# Power.net
KiCad netlist of a schematic drawn in Altium Designer
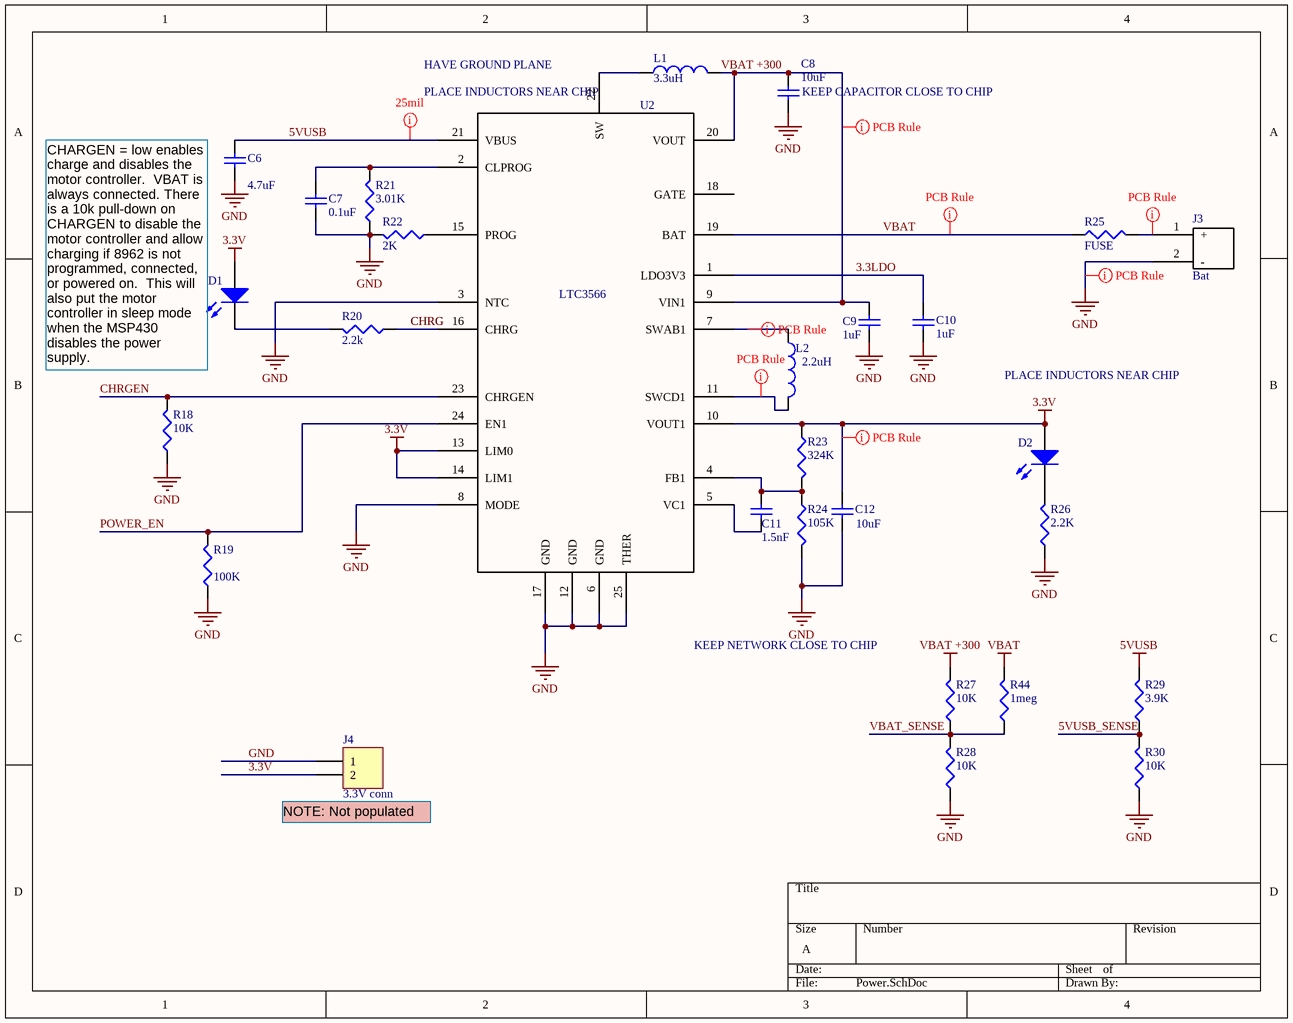
[diagram p0: Power.SchDoc]

(export (version "E")
  (design (tool "Eeschema 10.0.6"))
  (components
    (comp (ref "C6")
      (value "4.7uF")
      (footprint "CAPC1005L")
      (description "Capacitor (Semiconductor SIM Model)")
      (fields (field (name "Comment") "Cap Semi") (field (name "PUBLISHER") "Altium Limited"))
      (libsource (lib "Miscellaneous Devices") (part "Cap Semi"))
    )
    (comp (ref "C7")
      (value "0.1uF")
      (footprint "CAPC1005L")
      (description "Capacitor")
      (fields (field (name "Comment") "Cap") (field (name "PUBLISHER") "Altium Limited"))
      (libsource (lib "Miscellaneous Devices") (part "Cap"))
    )
    (comp (ref "C8")
      (value "10uF")
      (footprint "CAPC1608L")
      (description "Capacitor")
      (fields (field (name "Comment") "Cap") (field (name "PUBLISHER") "Altium Limited"))
      (libsource (lib "Miscellaneous Devices") (part "Cap"))
    )
    (comp (ref "C9")
      (value "1uF")
      (footprint "CAPC1608L")
      (description "Capacitor")
      (fields (field (name "Comment") "Cap") (field (name "PUBLISHER") "Altium Limited"))
      (libsource (lib "Miscellaneous Devices") (part "Cap"))
    )
    (comp (ref "C10")
      (value "1uF")
      (footprint "CAPC1608L")
      (description "Capacitor")
      (fields (field (name "Comment") "Cap") (field (name "PUBLISHER") "Altium Limited"))
      (libsource (lib "Miscellaneous Devices") (part "Cap"))
    )
    (comp (ref "C11")
      (value "1.5nF")
      (footprint "CAPC1005L")
      (description "Capacitor")
      (fields (field (name "Comment") "Cap") (field (name "PUBLISHER") "Altium Limited"))
      (libsource (lib "Miscellaneous Devices") (part "Cap"))
    )
    (comp (ref "C12")
      (value "10uF")
      (footprint "CAPC1608L")
      (description "Capacitor")
      (fields (field (name "Comment") "Cap") (field (name "PUBLISHER") "Altium Limited"))
      (libsource (lib "Miscellaneous Devices") (part "Cap"))
    )
    (comp (ref "D1")
      (value "Charge")
      (footprint "INDC2012L")
      (description "Typical RED, GREEN, YELLOW, AMBER GaAs LED")
      (fields (field (name "PUBLISHER") "Altium Limited"))
      (libsource (lib "Miscellaneous Devices") (part "LED2"))
    )
    (comp (ref "D2")
      (value "Power")
      (footprint "INDC2012L")
      (description "Typical RED, GREEN, YELLOW, AMBER GaAs LED")
      (fields (field (name "PUBLISHER") "Altium Limited"))
      (libsource (lib "Miscellaneous Devices") (part "LED2"))
    )
    (comp (ref "J3")
      (value "Bat")
      (footprint "BatteryConnJST")
      (libsource (lib "mrone") (part "BatteryConnJST"))
    )
    (comp (ref "J4")
      (value "3.3V conn")
      (footprint "HDR1X2")
      (description "Header, 2-Pin")
      (fields (field (name "PUBLISHER") "Altium Limited"))
      (libsource (lib "Miscellaneous Connectors") (part "Header 2"))
    )
    (comp (ref "L1") (value "3.3uH") (footprint "IndPow") (libsource (lib "mrone") (part "Inductor")))
    (comp (ref "L2") (value "2.2uH") (footprint "IndPow") (libsource (lib "mrone") (part "Inductor")))
    (comp (ref "R18")
      (value "10K")
      (footprint "RESC1608L")
      (description "Resistor")
      (fields (field (name "Comment") "Res3") (field (name "PUBLISHER") "Altium Limited"))
      (libsource (lib "Miscellaneous Devices") (part "Res3"))
    )
    (comp (ref "R19")
      (value "100K")
      (footprint "RESC1608L")
      (description "Resistor")
      (fields (field (name "Comment") "Res3") (field (name "PUBLISHER") "Altium Limited"))
      (libsource (lib "Miscellaneous Devices") (part "Res3"))
    )
    (comp (ref "R20")
      (value "2.2k")
      (footprint "RESC1608L")
      (description "Resistor")
      (fields (field (name "Comment") "Res3") (field (name "PUBLISHER") "Altium Limited"))
      (libsource (lib "Miscellaneous Devices") (part "Res3"))
    )
    (comp (ref "R21")
      (value "3.01K")
      (footprint "RESC1608L")
      (description "Resistor")
      (fields (field (name "Comment") "Res3") (field (name "PUBLISHER") "Altium Limited"))
      (libsource (lib "Miscellaneous Devices") (part "Res3"))
    )
    (comp (ref "R22")
      (value "2K")
      (footprint "RESC1608L")
      (description "Resistor")
      (fields (field (name "Comment") "Res3") (field (name "PUBLISHER") "Altium Limited"))
      (libsource (lib "Miscellaneous Devices") (part "Res3"))
    )
    (comp (ref "R23")
      (value "324K")
      (footprint "RESC1608L")
      (description "Resistor")
      (fields (field (name "Comment") "Res3") (field (name "PUBLISHER") "Altium Limited"))
      (libsource (lib "Miscellaneous Devices") (part "Res3"))
    )
    (comp (ref "R24")
      (value "105K")
      (footprint "RESC1608L")
      (description "Resistor")
      (fields (field (name "Comment") "Res3") (field (name "PUBLISHER") "Altium Limited"))
      (libsource (lib "Miscellaneous Devices") (part "Res3"))
    )
    (comp (ref "R25")
      (value "FUSE")
      (footprint "RESC3225L")
      (description "Resistor")
      (fields (field (name "Comment") "Res3") (field (name "PUBLISHER") "Altium Limited"))
      (libsource (lib "Miscellaneous Devices") (part "Res3"))
    )
    (comp (ref "R26")
      (value "2.2K")
      (footprint "RESC1608L")
      (description "Resistor")
      (fields (field (name "Comment") "Res3") (field (name "PUBLISHER") "Altium Limited"))
      (libsource (lib "Miscellaneous Devices") (part "Res3"))
    )
    (comp (ref "R27")
      (value "10K")
      (footprint "RESC1608L")
      (description "Resistor")
      (fields (field (name "Comment") "Res3") (field (name "PUBLISHER") "Altium Limited"))
      (libsource (lib "Miscellaneous Devices") (part "Res3"))
    )
    (comp (ref "R28")
      (value "10K")
      (footprint "RESC1608L")
      (description "Resistor")
      (fields (field (name "Comment") "Res3") (field (name "PUBLISHER") "Altium Limited"))
      (libsource (lib "Miscellaneous Devices") (part "Res3"))
    )
    (comp (ref "R29")
      (value "3.9K")
      (footprint "RESC1608L")
      (description "Resistor")
      (fields (field (name "Comment") "Res3") (field (name "PUBLISHER") "Altium Limited"))
      (libsource (lib "Miscellaneous Devices") (part "Res3"))
    )
    (comp (ref "R30")
      (value "10K")
      (footprint "RESC1608L")
      (description "Resistor")
      (fields (field (name "Comment") "Res3") (field (name "PUBLISHER") "Altium Limited"))
      (libsource (lib "Miscellaneous Devices") (part "Res3"))
    )
    (comp (ref "R44")
      (value "1meg")
      (footprint "RESC1608L")
      (description "Resistor")
      (fields (field (name "Comment") "Res3") (field (name "PUBLISHER") "Altium Limited"))
      (libsource (lib "Miscellaneous Devices") (part "Res3"))
    )
    (comp (ref "U2")
      (value "LTC3566")
      (footprint "QFN-24")
      (libsource (lib "Schematic Components") (part "LTC3566"))
    )
  )
  (nets
    (net (code "1") (name "/3.3LDO") (class "Default")
      (node (ref "C10") (pin "1") (pinfunction "1_1") (pintype "passive"))
      (node (ref "U2") (pin "1") (pinfunction "LDO3V3_1") (pintype "passive"))
    )
    (net (code "2") (name "/5VUSB_SENSE") (class "Default")
      (node (ref "R29") (pin "1") (pinfunction "1_1") (pintype "passive"))
      (node (ref "R30") (pin "2") (pinfunction "2_2") (pintype "passive"))
    )
    (net (code "3") (name "/CHRG") (class "Default")
      (node (ref "R20") (pin "1") (pinfunction "1_1") (pintype "passive"))
      (node (ref "U2") (pin "16") (pinfunction "CHRG_16") (pintype "passive"))
    )
    (net (code "4") (name "/CHRGEN") (class "Default")
      (node (ref "R18") (pin "2") (pinfunction "2_2") (pintype "passive"))
      (node (ref "U2") (pin "23") (pinfunction "CHRGEN_23") (pintype "passive"))
    )
    (net (code "5") (name "/POWER_EN") (class "Default")
      (node (ref "R19") (pin "2") (pinfunction "2_2") (pintype "passive"))
      (node (ref "U2") (pin "24") (pinfunction "EN1_24") (pintype "passive"))
    )
    (net (code "6") (name "/VBAT_SENSE") (class "Default")
      (node (ref "R27") (pin "1") (pinfunction "1_1") (pintype "passive"))
      (node (ref "R28") (pin "2") (pinfunction "2_2") (pintype "passive"))
      (node (ref "R44") (pin "1") (pinfunction "1_1") (pintype "passive"))
    )
    (net (code "7") (name "3.3V") (class "Default")
      (node (ref "C12") (pin "2") (pinfunction "2_2") (pintype "passive"))
      (node (ref "D1") (pin "1") (pinfunction "A_1") (pintype "passive"))
      (node (ref "D2") (pin "1") (pinfunction "A_1") (pintype "passive"))
      (node (ref "J4") (pin "2") (pinfunction "2_2") (pintype "passive"))
      (node (ref "R23") (pin "1") (pinfunction "1_1") (pintype "passive"))
      (node (ref "U2") (pin "10") (pinfunction "VOUT1_10") (pintype "passive"))
      (node (ref "U2") (pin "13") (pinfunction "LIM0_13") (pintype "passive"))
      (node (ref "U2") (pin "14") (pinfunction "LIM1_14") (pintype "passive"))
    )
    (net (code "8") (name "5VUSB") (class "Default")
      (node (ref "C6") (pin "2") (pinfunction "2_2") (pintype "passive"))
      (node (ref "R29") (pin "2") (pinfunction "2_2") (pintype "passive"))
      (node (ref "U2") (pin "21") (pinfunction "VBUS_21") (pintype "passive"))
    )
    (net (code "9") (name "GND") (class "Default")
      (node (ref "C10") (pin "2") (pinfunction "2_2") (pintype "passive"))
      (node (ref "C12") (pin "1") (pinfunction "1_1") (pintype "passive"))
      (node (ref "C6") (pin "1") (pinfunction "1_1") (pintype "passive"))
      (node (ref "C7") (pin "1") (pinfunction "1_1") (pintype "passive"))
      (node (ref "C8") (pin "1") (pinfunction "1_1") (pintype "passive"))
      (node (ref "C9") (pin "2") (pinfunction "2_2") (pintype "passive"))
      (node (ref "J3") (pin "2") (pinfunction "-_2") (pintype "passive"))
      (node (ref "J4") (pin "1") (pinfunction "1_1") (pintype "passive"))
      (node (ref "R18") (pin "1") (pinfunction "1_1") (pintype "passive"))
      (node (ref "R19") (pin "1") (pinfunction "1_1") (pintype "passive"))
      (node (ref "R21") (pin "1") (pinfunction "1_1") (pintype "passive"))
      (node (ref "R22") (pin "2") (pinfunction "2_2") (pintype "passive"))
      (node (ref "R24") (pin "2") (pinfunction "2_2") (pintype "passive"))
      (node (ref "R26") (pin "1") (pinfunction "1_1") (pintype "passive"))
      (node (ref "R28") (pin "1") (pinfunction "1_1") (pintype "passive"))
      (node (ref "R30") (pin "1") (pinfunction "1_1") (pintype "passive"))
      (node (ref "U2") (pin "12") (pinfunction "GND_12") (pintype "passive"))
      (node (ref "U2") (pin "17") (pinfunction "GND_17") (pintype "passive"))
      (node (ref "U2") (pin "25") (pinfunction "THER_25") (pintype "passive"))
      (node (ref "U2") (pin "3") (pinfunction "NTC_3") (pintype "passive"))
      (node (ref "U2") (pin "6") (pinfunction "GND_6") (pintype "passive"))
      (node (ref "U2") (pin "8") (pinfunction "MODE_8") (pintype "passive"))
    )
    (net (code "10") (name "Net-(D1-K)") (class "Default")
      (node (ref "D1") (pin "2") (pinfunction "K_2") (pintype "passive"))
      (node (ref "R20") (pin "2") (pinfunction "2_2") (pintype "passive"))
    )
    (net (code "11") (name "Net-(D2-K)") (class "Default")
      (node (ref "D2") (pin "2") (pinfunction "K_2") (pintype "passive"))
      (node (ref "R26") (pin "2") (pinfunction "2_2") (pintype "passive"))
    )
    (net (code "12") (name "Net-(J3-+)") (class "Default")
      (node (ref "J3") (pin "1") (pinfunction "+_1") (pintype "passive"))
      (node (ref "R25") (pin "2") (pinfunction "2_2") (pintype "passive"))
    )
    (net (code "13") (name "Net-(U2-CLPROG)") (class "Default")
      (node (ref "C7") (pin "2") (pinfunction "2_2") (pintype "passive"))
      (node (ref "R21") (pin "2") (pinfunction "2_2") (pintype "passive"))
      (node (ref "U2") (pin "2") (pinfunction "CLPROG_2") (pintype "passive"))
    )
    (net (code "14") (name "Net-(U2-FB1)") (class "Default")
      (node (ref "C11") (pin "1") (pinfunction "1_1") (pintype "passive"))
      (node (ref "R23") (pin "2") (pinfunction "2_2") (pintype "passive"))
      (node (ref "R24") (pin "1") (pinfunction "1_1") (pintype "passive"))
      (node (ref "U2") (pin "4") (pinfunction "FB1_4") (pintype "passive"))
    )
    (net (code "15") (name "Net-(U2-PROG)") (class "Default")
      (node (ref "R22") (pin "1") (pinfunction "1_1") (pintype "passive"))
      (node (ref "U2") (pin "15") (pinfunction "PROG_15") (pintype "passive"))
    )
    (net (code "16") (name "Net-(U2-SW)") (class "Default")
      (node (ref "L1") (pin "1") (pinfunction "1_1") (pintype "passive"))
      (node (ref "U2") (pin "22") (pinfunction "SW_22") (pintype "passive"))
    )
    (net (code "17") (name "Net-(U2-SWAB1)") (class "Default")
      (node (ref "L2") (pin "1") (pinfunction "1_1") (pintype "passive"))
      (node (ref "U2") (pin "7") (pinfunction "SWAB1_7") (pintype "passive"))
    )
    (net (code "18") (name "Net-(U2-SWCD1)") (class "Default")
      (node (ref "L2") (pin "2") (pinfunction "2_2") (pintype "passive"))
      (node (ref "U2") (pin "11") (pinfunction "SWCD1_11") (pintype "passive"))
    )
    (net (code "19") (name "Net-(U2-VC1)") (class "Default")
      (node (ref "C11") (pin "2") (pinfunction "2_2") (pintype "passive"))
      (node (ref "U2") (pin "5") (pinfunction "VC1_5") (pintype "passive"))
    )
    (net (code "20") (name "VBAT") (class "Default")
      (node (ref "R25") (pin "1") (pinfunction "1_1") (pintype "passive"))
      (node (ref "R44") (pin "2") (pinfunction "2_2") (pintype "passive"))
      (node (ref "U2") (pin "19") (pinfunction "BAT_19") (pintype "passive"))
    )
    (net (code "21") (name "VBAT +300") (class "Default")
      (node (ref "C8") (pin "2") (pinfunction "2_2") (pintype "passive"))
      (node (ref "C9") (pin "1") (pinfunction "1_1") (pintype "passive"))
      (node (ref "L1") (pin "2") (pinfunction "2_2") (pintype "passive"))
      (node (ref "R27") (pin "2") (pinfunction "2_2") (pintype "passive"))
      (node (ref "U2") (pin "20") (pinfunction "VOUT_20") (pintype "passive"))
      (node (ref "U2") (pin "9") (pinfunction "VIN1_9") (pintype "passive"))
    )
    (net (code "22") (name "unconnected-(U2-GATE-Pad18)") (class "Default")
      (node (ref "U2") (pin "18") (pinfunction "GATE_18") (pintype "passive"))
    )
  )
)
